# Reflow_Oven_V1_1.net
KiCad netlist of a schematic drawn in EAGLE
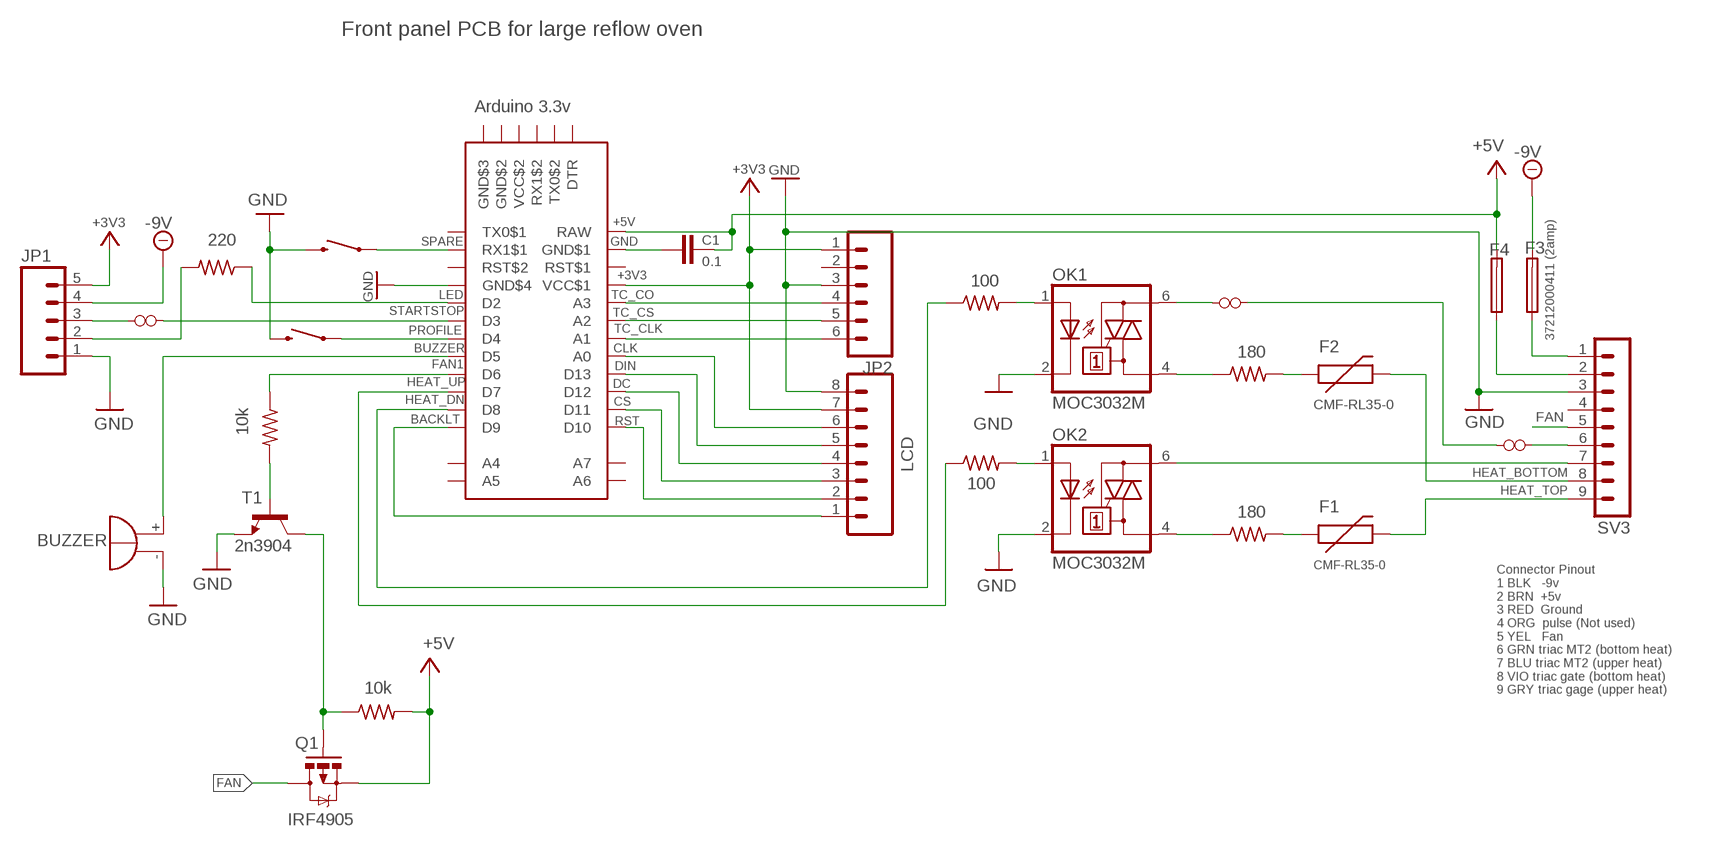
[diagram p0: schematic, sheet 1]

(export (version "E")
  (design (tool "Eeschema 10.0.6"))
  (components
    (comp (ref "BUZZER")
      (value "F/HMB")
      (footprint "eagle-import:F_HMB")
      (libsource (lib "eagle-import") (part "F/HMB"))
    )
    (comp (ref "C1")
      (value "0.1")
      (footprint "eagle-import:CAP-PTH-SMALL")
      (libsource (lib "eagle-import") (part "CAPPTH"))
    )
    (comp (ref "F1")
      (value "CMF-RL35-0")
      (footprint "eagle-import:PTC")
      (libsource (lib "eagle-import") (part "PTCPTH"))
    )
    (comp (ref "F2")
      (value "CMF-RL35-0")
      (footprint "eagle-import:PTC")
      (libsource (lib "eagle-import") (part "PTCPTH"))
    )
    (comp (ref "F3")
      (value "37212000411 (2amp)")
      (footprint "eagle-import:19560")
      (fields (field (name "MPN") "56000001009"))
      (libsource (lib "eagle-import") (part "19560"))
    )
    (comp (ref "F4")
      (value "37212000411 (2amp)")
      (footprint "eagle-import:19560")
      (fields (field (name "MPN") "56000001009"))
      (libsource (lib "eagle-import") (part "19560"))
    )
    (comp (ref "JP1")
      (value "M05PTH")
      (footprint "eagle-import:1X05")
      (libsource (lib "eagle-import") (part "M05PTH"))
    )
    (comp (ref "JP2")
      (value "M06SIP")
      (footprint "eagle-import:1X06")
      (libsource (lib "eagle-import") (part "M06SIP"))
    )
    (comp (ref "LCD")
      (value "M081X08")
      (footprint "eagle-import:1X08")
      (libsource (lib "eagle-import") (part "M081X08"))
    )
    (comp (ref "OK1")
      (value "MOC3032M")
      (footprint "eagle-import:DIL06")
      (fields (field (name "MF") "FAIRCHILD SEMICONDUCTOR") (field (name "MPN") "MOC3032-M"))
      (libsource (lib "eagle-import") (part "MOC3032M"))
    )
    (comp (ref "OK2")
      (value "MOC3032M")
      (footprint "eagle-import:DIL06")
      (fields (field (name "MF") "FAIRCHILD SEMICONDUCTOR") (field (name "MPN") "MOC3032-M"))
      (libsource (lib "eagle-import") (part "MOC3032M"))
    )
    (comp (ref "PROFILE")
      (value "SWITCH-MOMENTARY-2PTH")
      (footprint "eagle-import:TACTILE-PTH")
      (libsource (lib "eagle-import") (part "SWITCH-MOMENTARY-2PTH"))
    )
    (comp (ref "Q1")
      (value "IRF4905")
      (footprint "eagle-import:TO220V")
      (libsource (lib "eagle-import") (part "MOSFET-PCHANNELFQP27P06"))
    )
    (comp (ref "R2")
      (value "100")
      (footprint "eagle-import:0207_10")
      (libsource (lib "eagle-import") (part "R-US_0207/10"))
    )
    (comp (ref "R3")
      (value "180")
      (footprint "eagle-import:0207_12")
      (libsource (lib "eagle-import") (part "R-US_0207/12"))
    )
    (comp (ref "R4")
      (value "180")
      (footprint "eagle-import:0207_12")
      (libsource (lib "eagle-import") (part "R-US_0207/12"))
    )
    (comp (ref "R5")
      (value "100")
      (footprint "eagle-import:0207_10")
      (libsource (lib "eagle-import") (part "R-US_0207/10"))
    )
    (comp (ref "R11")
      (value "10k")
      (footprint "eagle-import:0207_10")
      (libsource (lib "eagle-import") (part "R-US_0207/10"))
    )
    (comp (ref "R12")
      (value "220")
      (footprint "eagle-import:0207_10")
      (libsource (lib "eagle-import") (part "R-US_0207/10"))
    )
    (comp (ref "R13")
      (value "10k")
      (footprint "eagle-import:0207_10")
      (libsource (lib "eagle-import") (part "R-US_0207/10"))
    )
    (comp (ref "SPARE")
      (value "SWITCH-MOMENTARY-2PTH")
      (footprint "eagle-import:TACTILE-PTH")
      (libsource (lib "eagle-import") (part "SWITCH-MOMENTARY-2PTH"))
    )
    (comp (ref "SV3")
      (value "MA09-1")
      (footprint "eagle-import:MA09-1")
      (libsource (lib "eagle-import") (part "MA09-1"))
    )
    (comp (ref "T1")
      (value "2n3904")
      (footprint "eagle-import:TO92-EBC")
      (libsource (lib "eagle-import") (part "-NPN-TO92-EBC2N3904"))
    )
    (comp (ref "U$1")
      (value "JUMPER0.3_INCH")
      (footprint "eagle-import:JUMPER_0.3")
      (libsource (lib "eagle-import") (part "JUMPER0.3_INCH"))
    )
    (comp (ref "U$2")
      (value "Arduino 3.3v")
      (footprint "eagle-import:ARDUINO_PRO_MINI")
      (libsource (lib "eagle-import") (part "ARDUINO_PRO_MINI"))
    )
    (comp (ref "U$4")
      (value "JUMPER0.3_INCH")
      (footprint "eagle-import:JUMPER_0.3")
      (libsource (lib "eagle-import") (part "JUMPER0.3_INCH"))
    )
    (comp (ref "U$5")
      (value "JUMPER0.7INCH")
      (footprint "eagle-import:JUMPER_0.7")
      (libsource (lib "eagle-import") (part "JUMPER0.7INCH"))
    )
  )
  (nets
    (net (code "1") (name "+3V3") (class "Default")
      (node (ref "JP1") (pin "5") (pinfunction "5_5") (pintype "passive"))
      (node (ref "JP2") (pin "1") (pinfunction "1_1") (pintype "passive"))
      (node (ref "LCD") (pin "7") (pinfunction "7_7") (pintype "passive"))
      (node (ref "U$2") (pin "VCC$1") (pinfunction "VCC$1_VCC$1") (pintype "power_in"))
    )
    (net (code "2") (name "+5V") (class "Default")
      (node (ref "C1") (pin "1") (pinfunction "1_1") (pintype "passive"))
      (node (ref "F4") (pin "2") (pinfunction "2_2") (pintype "passive"))
      (node (ref "Q1") (pin "3") (pinfunction "S_3") (pintype "passive"))
      (node (ref "R13") (pin "2") (pinfunction "2_2") (pintype "passive"))
      (node (ref "U$2") (pin "RAW") (pinfunction "RAW_RAW") (pintype "power_in"))
    )
    (net (code "3") (name "-9V") (class "Default")
      (node (ref "F3") (pin "2") (pinfunction "2_2") (pintype "passive"))
      (node (ref "JP1") (pin "4") (pinfunction "4_4") (pintype "passive"))
    )
    (net (code "4") (name "/BACKLT") (class "Default")
      (node (ref "LCD") (pin "1") (pinfunction "1_1") (pintype "passive"))
      (node (ref "U$2") (pin "D9") (pinfunction "D9_D9") (pintype "bidirectional"))
    )
    (net (code "5") (name "/BUZZER") (class "Default")
      (node (ref "BUZZER") (pin "+") (pinfunction "+_+") (pintype "passive"))
      (node (ref "U$2") (pin "D5") (pinfunction "D5_D5") (pintype "bidirectional"))
    )
    (net (code "6") (name "/CLK") (class "Default")
      (node (ref "LCD") (pin "6") (pinfunction "6_6") (pintype "passive"))
      (node (ref "U$2") (pin "A0") (pinfunction "A0_A0") (pintype "bidirectional"))
    )
    (net (code "7") (name "/CS") (class "Default")
      (node (ref "LCD") (pin "3") (pinfunction "3_3") (pintype "passive"))
      (node (ref "U$2") (pin "D11") (pinfunction "D11_D11") (pintype "bidirectional"))
    )
    (net (code "8") (name "/DC") (class "Default")
      (node (ref "LCD") (pin "4") (pinfunction "4_4") (pintype "passive"))
      (node (ref "U$2") (pin "D12") (pinfunction "D12_D12") (pintype "bidirectional"))
    )
    (net (code "9") (name "/DIN") (class "Default")
      (node (ref "LCD") (pin "5") (pinfunction "5_5") (pintype "passive"))
      (node (ref "U$2") (pin "D13") (pinfunction "D13_D13") (pintype "bidirectional"))
    )
    (net (code "10") (name "/FAN1") (class "Default")
      (node (ref "R11") (pin "1") (pinfunction "1_1") (pintype "passive"))
      (node (ref "U$2") (pin "D6") (pinfunction "D6_D6") (pintype "bidirectional"))
    )
    (net (code "11") (name "/GND$2") (class "Default")
      (node (ref "U$2") (pin "GND$2") (pinfunction "GND$2_GND$2") (pintype "power_in"))
    )
    (net (code "12") (name "/GND$3") (class "Default")
      (node (ref "U$2") (pin "GND$3") (pinfunction "GND$3_GND$3") (pintype "power_in"))
    )
    (net (code "13") (name "/HEAT_BOTTOM") (class "Default")
      (node (ref "F2") (pin "P$2") (pinfunction "2_P$2") (pintype "bidirectional"))
      (node (ref "SV3") (pin "8") (pinfunction "8_8") (pintype "passive"))
    )
    (net (code "14") (name "/HEAT_DN") (class "Default")
      (node (ref "R5") (pin "1") (pinfunction "1_1") (pintype "passive"))
      (node (ref "U$2") (pin "D8") (pinfunction "D8_D8") (pintype "bidirectional"))
    )
    (net (code "15") (name "/HEAT_TOP") (class "Default")
      (node (ref "F1") (pin "P$2") (pinfunction "2_P$2") (pintype "bidirectional"))
      (node (ref "SV3") (pin "9") (pinfunction "9_9") (pintype "passive"))
    )
    (net (code "16") (name "/HEAT_UP") (class "Default")
      (node (ref "R2") (pin "1") (pinfunction "1_1") (pintype "passive"))
      (node (ref "U$2") (pin "D7") (pinfunction "D7_D7") (pintype "bidirectional"))
    )
    (net (code "17") (name "/LED") (class "Default")
      (node (ref "R12") (pin "1") (pinfunction "1_1") (pintype "passive"))
      (node (ref "U$2") (pin "D2") (pinfunction "D2_D2") (pintype "bidirectional"))
    )
    (net (code "18") (name "/PROFILE") (class "Default")
      (node (ref "PROFILE") (pin "1") (pinfunction "1_1") (pintype "passive"))
      (node (ref "U$2") (pin "D4") (pinfunction "D4_D4") (pintype "bidirectional"))
    )
    (net (code "19") (name "/RST") (class "Default")
      (node (ref "LCD") (pin "2") (pinfunction "2_2") (pintype "passive"))
      (node (ref "U$2") (pin "D10") (pinfunction "D10_D10") (pintype "bidirectional"))
    )
    (net (code "20") (name "/SPARE") (class "Default")
      (node (ref "SPARE") (pin "1") (pinfunction "1_1") (pintype "passive"))
      (node (ref "U$2") (pin "RX1$1") (pinfunction "RX1$1_RX1$1") (pintype "bidirectional"))
    )
    (net (code "21") (name "/STARTSTOP") (class "Default")
      (node (ref "U$2") (pin "D3") (pinfunction "D3_D3") (pintype "bidirectional"))
      (node (ref "U$4") (pin "P$2") (pinfunction "P$2_P$2") (pintype "bidirectional"))
    )
    (net (code "22") (name "/TC_CLK") (class "Default")
      (node (ref "JP2") (pin "6") (pinfunction "6_6") (pintype "passive"))
      (node (ref "U$2") (pin "A1") (pinfunction "A1_A1") (pintype "bidirectional"))
    )
    (net (code "23") (name "/TC_CO") (class "Default")
      (node (ref "JP2") (pin "4") (pinfunction "4_4") (pintype "passive"))
      (node (ref "U$2") (pin "A3") (pinfunction "A3_A3") (pintype "bidirectional"))
    )
    (net (code "24") (name "/TC_CS") (class "Default")
      (node (ref "JP2") (pin "5") (pinfunction "5_5") (pintype "passive"))
      (node (ref "U$2") (pin "A2") (pinfunction "A2_A2") (pintype "bidirectional"))
    )
    (net (code "25") (name "/VCC$2") (class "Default")
      (node (ref "U$2") (pin "VCC$2") (pinfunction "VCC$2_VCC$2") (pintype "power_in"))
    )
    (net (code "26") (name "FAN") (class "Default")
      (node (ref "Q1") (pin "2") (pinfunction "D_2") (pintype "passive"))
      (node (ref "SV3") (pin "5") (pinfunction "5_5") (pintype "passive"))
    )
    (net (code "27") (name "GND") (class "Default")
      (node (ref "BUZZER") (pin "-") (pinfunction "-_-") (pintype "passive"))
      (node (ref "JP1") (pin "1") (pinfunction "1_1") (pintype "passive"))
      (node (ref "JP2") (pin "3") (pinfunction "3_3") (pintype "passive"))
      (node (ref "LCD") (pin "8") (pinfunction "8_8") (pintype "passive"))
      (node (ref "OK1") (pin "2") (pinfunction "C_2") (pintype "passive"))
      (node (ref "OK2") (pin "2") (pinfunction "C_2") (pintype "passive"))
      (node (ref "PROFILE") (pin "3") (pinfunction "2_3") (pintype "passive"))
      (node (ref "SPARE") (pin "3") (pinfunction "2_3") (pintype "passive"))
      (node (ref "SV3") (pin "3") (pinfunction "3_3") (pintype "passive"))
      (node (ref "T1") (pin "E") (pinfunction "E_E") (pintype "passive"))
      (node (ref "U$2") (pin "GND$4") (pinfunction "GND$4_GND$4") (pintype "power_in"))
    )
    (net (code "28") (name "Net-(F1-1)") (class "Default")
      (node (ref "F1") (pin "P$1") (pinfunction "1_P$1") (pintype "bidirectional"))
      (node (ref "R4") (pin "2") (pinfunction "2_2") (pintype "passive"))
    )
    (net (code "29") (name "Net-(F2-1)") (class "Default")
      (node (ref "F2") (pin "P$1") (pinfunction "1_P$1") (pintype "bidirectional"))
      (node (ref "R3") (pin "2") (pinfunction "2_2") (pintype "passive"))
    )
    (net (code "30") (name "Net-(F3-Pad1)") (class "Default")
      (node (ref "F3") (pin "1") (pinfunction "1_1") (pintype "passive"))
      (node (ref "SV3") (pin "1") (pinfunction "1_1") (pintype "passive"))
    )
    (net (code "31") (name "Net-(F4-Pad1)") (class "Default")
      (node (ref "F4") (pin "1") (pinfunction "1_1") (pintype "passive"))
      (node (ref "SV3") (pin "2") (pinfunction "2_2") (pintype "passive"))
    )
    (net (code "32") (name "Net-(JP1-Pad2)") (class "Default")
      (node (ref "JP1") (pin "2") (pinfunction "2_2") (pintype "passive"))
      (node (ref "R12") (pin "2") (pinfunction "2_2") (pintype "passive"))
    )
    (net (code "33") (name "Net-(JP1-Pad3)") (class "Default")
      (node (ref "JP1") (pin "3") (pinfunction "3_3") (pintype "passive"))
      (node (ref "U$4") (pin "P$1") (pinfunction "P$1_P$1") (pintype "bidirectional"))
    )
    (net (code "34") (name "Net-(OK1-A)") (class "Default")
      (node (ref "OK1") (pin "1") (pinfunction "A_1") (pintype "passive"))
      (node (ref "R5") (pin "2") (pinfunction "2_2") (pintype "passive"))
    )
    (net (code "35") (name "Net-(OK1-A1)") (class "Default")
      (node (ref "OK1") (pin "4") (pinfunction "A1_4") (pintype "passive"))
      (node (ref "R3") (pin "1") (pinfunction "1_1") (pintype "passive"))
    )
    (net (code "36") (name "Net-(OK1-A2)") (class "Default")
      (node (ref "OK1") (pin "6") (pinfunction "A2_6") (pintype "passive"))
      (node (ref "U$5") (pin "P$1") (pinfunction "P$1_P$1") (pintype "bidirectional"))
    )
    (net (code "37") (name "Net-(OK2-A)") (class "Default")
      (node (ref "OK2") (pin "1") (pinfunction "A_1") (pintype "passive"))
      (node (ref "R2") (pin "2") (pinfunction "2_2") (pintype "passive"))
    )
    (net (code "38") (name "Net-(OK2-A1)") (class "Default")
      (node (ref "OK2") (pin "4") (pinfunction "A1_4") (pintype "passive"))
      (node (ref "R4") (pin "1") (pinfunction "1_1") (pintype "passive"))
    )
    (net (code "39") (name "Net-(OK2-A2)") (class "Default")
      (node (ref "OK2") (pin "6") (pinfunction "A2_6") (pintype "passive"))
      (node (ref "SV3") (pin "7") (pinfunction "7_7") (pintype "passive"))
    )
    (net (code "40") (name "Net-(Q1-G)") (class "Default")
      (node (ref "Q1") (pin "1") (pinfunction "G_1") (pintype "passive"))
      (node (ref "R13") (pin "1") (pinfunction "1_1") (pintype "passive"))
      (node (ref "T1") (pin "C") (pinfunction "C_C") (pintype "passive"))
    )
    (net (code "41") (name "Net-(R11-Pad2)") (class "Default")
      (node (ref "R11") (pin "2") (pinfunction "2_2") (pintype "passive"))
      (node (ref "T1") (pin "B") (pinfunction "B_B") (pintype "passive"))
    )
    (net (code "42") (name "Net-(SV3-Pad6)") (class "Default")
      (node (ref "SV3") (pin "6") (pinfunction "6_6") (pintype "passive"))
      (node (ref "U$1") (pin "P$2") (pinfunction "P$2_P$2") (pintype "bidirectional"))
    )
    (net (code "43") (name "Net-(U$1-PadP$1)") (class "Default")
      (node (ref "U$1") (pin "P$1") (pinfunction "P$1_P$1") (pintype "bidirectional"))
      (node (ref "U$5") (pin "P$2") (pinfunction "P$2_P$2") (pintype "bidirectional"))
    )
    (net (code "44") (name "Net-(U$2-GND$1)") (class "Default")
      (node (ref "C1") (pin "2") (pinfunction "2_2") (pintype "passive"))
      (node (ref "U$2") (pin "GDN$1") (pinfunction "GND$1_GDN$1") (pintype "power_in"))
    )
    (net (code "45") (name "unconnected-(JP2-Pad2)") (class "Default")
      (node (ref "JP2") (pin "2") (pinfunction "2_2") (pintype "passive"))
    )
    (net (code "46") (name "unconnected-(SV3-Pad4)") (class "Default")
      (node (ref "SV3") (pin "4") (pinfunction "4_4") (pintype "passive"))
    )
    (net (code "47") (name "unconnected-(U$2-PadA4)") (class "Default")
      (node (ref "U$2") (pin "A4") (pinfunction "A4_A4") (pintype "bidirectional"))
    )
    (net (code "48") (name "unconnected-(U$2-PadA5)") (class "Default")
      (node (ref "U$2") (pin "A5") (pinfunction "A5_A5") (pintype "bidirectional"))
    )
    (net (code "49") (name "unconnected-(U$2-PadA6)") (class "Default")
      (node (ref "U$2") (pin "A6") (pinfunction "A6_A6") (pintype "input"))
    )
    (net (code "50") (name "unconnected-(U$2-PadA7)") (class "Default")
      (node (ref "U$2") (pin "A7") (pinfunction "A7_A7") (pintype "input"))
    )
    (net (code "51") (name "unconnected-(U$2-PadDTR)") (class "Default")
      (node (ref "U$2") (pin "DTR") (pinfunction "DTR_DTR") (pintype "input"))
    )
    (net (code "52") (name "unconnected-(U$2-PadRST$1)") (class "Default")
      (node (ref "U$2") (pin "RST$1") (pinfunction "RST$1_RST$1") (pintype "input"))
    )
    (net (code "53") (name "unconnected-(U$2-PadRST$2)") (class "Default")
      (node (ref "U$2") (pin "RST$2") (pinfunction "RST$2_RST$2") (pintype "input"))
    )
    (net (code "54") (name "unconnected-(U$2-PadRX1$2)") (class "Default")
      (node (ref "U$2") (pin "RX1$2") (pinfunction "RX1$2_RX1$2") (pintype "bidirectional"))
    )
    (net (code "55") (name "unconnected-(U$2-PadTX0$1)") (class "Default")
      (node (ref "U$2") (pin "TX0$1") (pinfunction "TX0$1_TX0$1") (pintype "bidirectional"))
    )
    (net (code "56") (name "unconnected-(U$2-PadTX0$2)") (class "Default")
      (node (ref "U$2") (pin "TX0$2") (pinfunction "TX0$2_TX0$2") (pintype "bidirectional"))
    )
  )
)
